# ttl_adapter.net
KiCad netlist of a schematic drawn in EAGLE
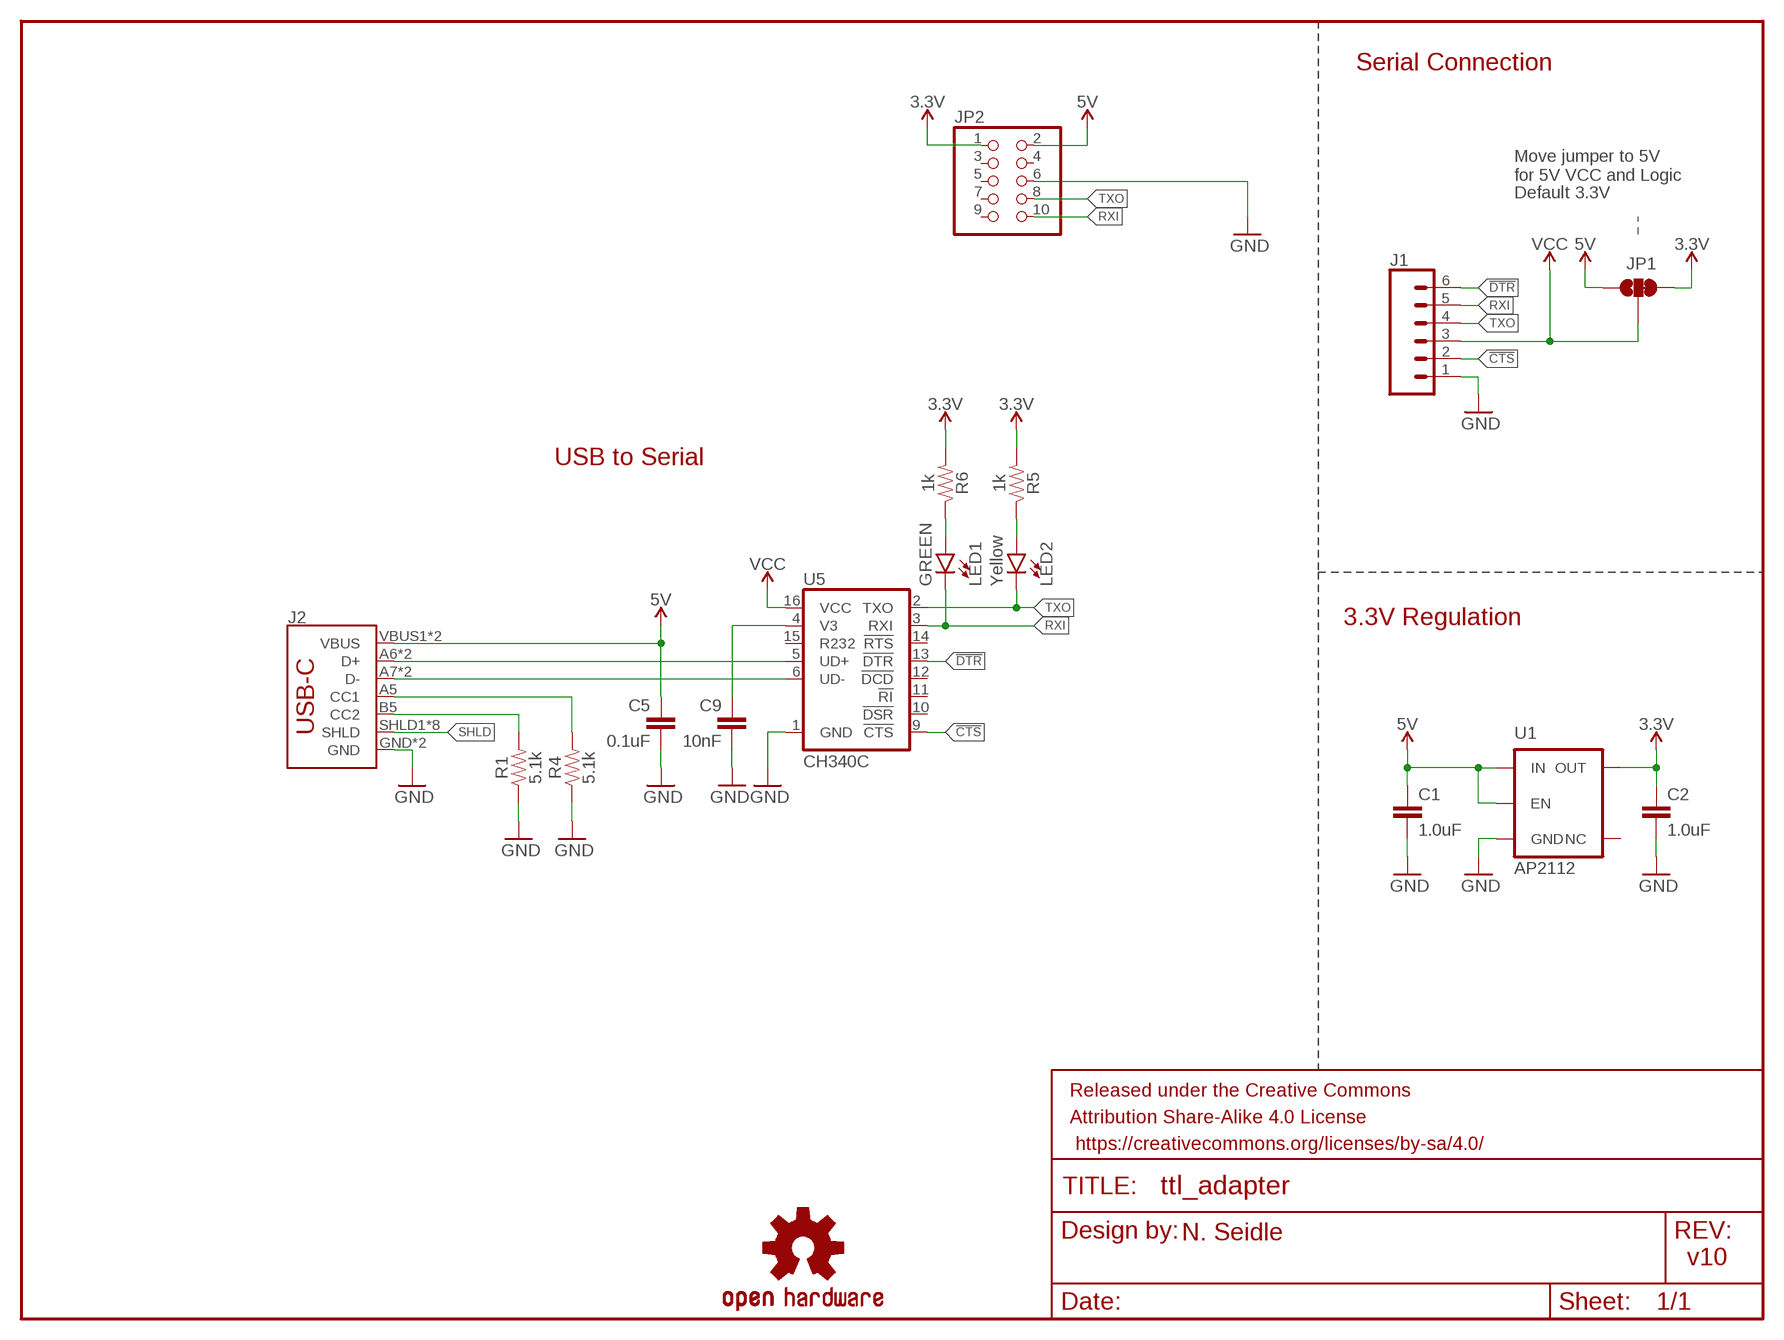
[diagram p0: schematic, sheet 1]

(export (version "E")
  (design (tool "Eeschema 10.0.6"))
  (components
    (comp (ref "C1")
      (value "1.0uF")
      (footprint "eagle-import:0603")
      (libsource (lib "eagle-import") (part "1.0UF-0603-16V-10%"))
    )
    (comp (ref "C2")
      (value "1.0uF")
      (footprint "eagle-import:0603")
      (libsource (lib "eagle-import") (part "1.0UF-0603-16V-10%"))
    )
    (comp (ref "C5")
      (value "0.1uF")
      (footprint "eagle-import:0603")
      (libsource (lib "eagle-import") (part "0.1UF-0603-25V-(+80/-20%)"))
    )
    (comp (ref "C9")
      (value "10nF")
      (footprint "eagle-import:0603")
      (libsource (lib "eagle-import") (part "10NF-0603-50V-10%"))
    )
    (comp (ref "FRAME1")
      (value "FRAME-LETTER")
      (footprint "eagle-import:CREATIVE_COMMONS")
      (libsource (lib "eagle-import") (part "FRAME-LETTER"))
    )
    (comp (ref "J1")
      (value "CONN_06SMD-FEMALE-V2")
      (footprint "eagle-import:1X06-SMD-FEMALE")
      (libsource (lib "eagle-import") (part "CONN_06SMD-FEMALE-V2"))
    )
    (comp (ref "J2")
      (value "USB_C16PIN")
      (footprint "eagle-import:USB-C-16P")
      (libsource (lib "eagle-import") (part "USB_C16PIN"))
    )
    (comp (ref "JP1")
      (value "JUMPER-SMT_3_1-NC_TRACE_SILK")
      (footprint "eagle-import:SMT-JUMPER_3_1-NC_TRACE_SILK")
      (libsource (lib "eagle-import") (part "JUMPER-SMT_3_1-NC_TRACE_SILK"))
    )
    (comp (ref "JP2")
      (value "PINHD-2X5")
      (footprint "eagle-import:2X05")
      (libsource (lib "eagle-import") (part "PINHD-2X5"))
    )
    (comp (ref "LED1")
      (value "GREEN")
      (footprint "eagle-import:LED-0603")
      (libsource (lib "eagle-import") (part "LED-GREEN0603"))
    )
    (comp (ref "LED2")
      (value "Yellow")
      (footprint "eagle-import:LED-0603")
      (libsource (lib "eagle-import") (part "LED-YELLOW0603"))
    )
    (comp (ref "LOGO1")
      (value "OSHW-LOGOS")
      (footprint "eagle-import:OSHW-LOGO-S")
      (libsource (lib "eagle-import") (part "OSHW-LOGOS"))
    )
    (comp (ref "R1")
      (value "5.1k")
      (footprint "eagle-import:0603")
      (libsource (lib "eagle-import") (part "5.1KOHM5.1KOHM-0603-1/10W-1%"))
    )
    (comp (ref "R4")
      (value "5.1k")
      (footprint "eagle-import:0603")
      (libsource (lib "eagle-import") (part "5.1KOHM5.1KOHM-0603-1/10W-1%"))
    )
    (comp (ref "R5")
      (value "1k")
      (footprint "eagle-import:0603")
      (libsource (lib "eagle-import") (part "1KOHM-0603-1/10W-1%"))
    )
    (comp (ref "R6")
      (value "1k")
      (footprint "eagle-import:0603")
      (libsource (lib "eagle-import") (part "1KOHM-0603-1/10W-1%"))
    )
    (comp (ref "U1")
      (value "3.3V")
      (footprint "eagle-import:SOT23-5")
      (libsource (lib "eagle-import") (part "V_REG_AP2112K-3.3V"))
    )
    (comp (ref "U5")
      (value "CH340C")
      (footprint "eagle-import:SO016")
      (libsource (lib "eagle-import") (part "CH340C"))
    )
  )
  (nets
    (net (code "1") (name "/~{CTS}") (class "Default")
      (node (ref "J1") (pin "2") (pinfunction "2_2") (pintype "passive"))
      (node (ref "U5") (pin "9") (pinfunction "~{CTS}_9") (pintype "bidirectional"))
    )
    (net (code "2") (name "/~{DTR}") (class "Default")
      (node (ref "J1") (pin "6") (pinfunction "6_6") (pintype "passive"))
      (node (ref "U5") (pin "13") (pinfunction "~{DTR}_13") (pintype "bidirectional"))
    )
    (net (code "3") (name "3.3V") (class "Default")
      (node (ref "C2") (pin "1") (pinfunction "1_1") (pintype "passive"))
      (node (ref "JP1") (pin "3") (pinfunction "3_3") (pintype "passive"))
      (node (ref "JP2") (pin "1") (pinfunction "1_1") (pintype "passive"))
      (node (ref "R5") (pin "2") (pinfunction "2_2") (pintype "passive"))
      (node (ref "R6") (pin "2") (pinfunction "2_2") (pintype "passive"))
      (node (ref "U1") (pin "5") (pinfunction "OUT_5") (pintype "passive"))
    )
    (net (code "4") (name "5V") (class "Default")
      (node (ref "C1") (pin "1") (pinfunction "1_1") (pintype "passive"))
      (node (ref "C5") (pin "1") (pinfunction "1_1") (pintype "passive"))
      (node (ref "J2") (pin "VBUS1") (pinfunction "VBUS_VBUS1") (pintype "bidirectional"))
      (node (ref "J2") (pin "VBUS2") (pinfunction "VBUS_VBUS2") (pintype "bidirectional"))
      (node (ref "JP1") (pin "1") (pinfunction "1_1") (pintype "passive"))
      (node (ref "JP2") (pin "2") (pinfunction "2_2") (pintype "passive"))
      (node (ref "U1") (pin "1") (pinfunction "IN_1") (pintype "input"))
      (node (ref "U1") (pin "3") (pinfunction "EN_3") (pintype "input"))
    )
    (net (code "5") (name "GND") (class "Default")
      (node (ref "C1") (pin "2") (pinfunction "2_2") (pintype "passive"))
      (node (ref "C2") (pin "2") (pinfunction "2_2") (pintype "passive"))
      (node (ref "C5") (pin "2") (pinfunction "2_2") (pintype "passive"))
      (node (ref "C9") (pin "2") (pinfunction "2_2") (pintype "passive"))
      (node (ref "J1") (pin "1") (pinfunction "1_1") (pintype "passive"))
      (node (ref "J2") (pin "GND") (pinfunction "GND_GND") (pintype "bidirectional"))
      (node (ref "J2") (pin "GND2") (pinfunction "GND_GND2") (pintype "bidirectional"))
      (node (ref "JP2") (pin "6") (pinfunction "6_6") (pintype "passive"))
      (node (ref "R1") (pin "1") (pinfunction "1_1") (pintype "passive"))
      (node (ref "R4") (pin "1") (pinfunction "1_1") (pintype "passive"))
      (node (ref "U1") (pin "2") (pinfunction "GND_2") (pintype "input"))
      (node (ref "U5") (pin "1") (pinfunction "GND_1") (pintype "bidirectional"))
    )
    (net (code "6") (name "Net-(J2-CC1)") (class "Default")
      (node (ref "J2") (pin "A5") (pinfunction "CC1_A5") (pintype "bidirectional"))
      (node (ref "R4") (pin "2") (pinfunction "2_2") (pintype "passive"))
    )
    (net (code "7") (name "Net-(J2-CC2)") (class "Default")
      (node (ref "J2") (pin "B5") (pinfunction "CC2_B5") (pintype "bidirectional"))
      (node (ref "R1") (pin "2") (pinfunction "2_2") (pintype "passive"))
    )
    (net (code "8") (name "Net-(LED1-PadA)") (class "Default")
      (node (ref "LED1") (pin "A") (pinfunction "A_A") (pintype "passive"))
      (node (ref "R6") (pin "1") (pinfunction "1_1") (pintype "passive"))
    )
    (net (code "9") (name "Net-(LED2-PadA)") (class "Default")
      (node (ref "LED2") (pin "A") (pinfunction "A_A") (pintype "passive"))
      (node (ref "R5") (pin "1") (pinfunction "1_1") (pintype "passive"))
    )
    (net (code "10") (name "Net-(U5-UD+)") (class "Default")
      (node (ref "J2") (pin "A6") (pinfunction "D+_A6") (pintype "bidirectional"))
      (node (ref "J2") (pin "B6") (pinfunction "D+_B6") (pintype "bidirectional"))
      (node (ref "U5") (pin "5") (pinfunction "UD+_5") (pintype "bidirectional"))
    )
    (net (code "11") (name "Net-(U5-UD-)") (class "Default")
      (node (ref "J2") (pin "A7") (pinfunction "D-_A7") (pintype "bidirectional"))
      (node (ref "J2") (pin "B7") (pinfunction "D-_B7") (pintype "bidirectional"))
      (node (ref "U5") (pin "6") (pinfunction "UD-_6") (pintype "bidirectional"))
    )
    (net (code "12") (name "Net-(U5-V3)") (class "Default")
      (node (ref "C9") (pin "1") (pinfunction "1_1") (pintype "passive"))
      (node (ref "U5") (pin "4") (pinfunction "V3_4") (pintype "bidirectional"))
    )
    (net (code "13") (name "RXI") (class "Default")
      (node (ref "J1") (pin "5") (pinfunction "5_5") (pintype "passive"))
      (node (ref "JP2") (pin "10") (pinfunction "10_10") (pintype "passive"))
      (node (ref "LED1") (pin "C") (pinfunction "C_C") (pintype "passive"))
      (node (ref "U5") (pin "3") (pinfunction "RXI_3") (pintype "bidirectional"))
    )
    (net (code "14") (name "SHLD") (class "Default")
      (node (ref "J2") (pin "SHLD1") (pinfunction "SHLD_SHLD1") (pintype "bidirectional"))
      (node (ref "J2") (pin "SHLD2") (pinfunction "SHLD_SHLD2") (pintype "bidirectional"))
      (node (ref "J2") (pin "SHLD3") (pinfunction "SHLD_SHLD3") (pintype "bidirectional"))
      (node (ref "J2") (pin "SHLD4") (pinfunction "SHLD_SHLD4") (pintype "bidirectional"))
      (node (ref "J2") (pin "SHLD5") (pinfunction "SHLD_SHLD5") (pintype "bidirectional"))
      (node (ref "J2") (pin "SHLD6") (pinfunction "SHLD_SHLD6") (pintype "bidirectional"))
      (node (ref "J2") (pin "SHLD7") (pinfunction "SHLD_SHLD7") (pintype "bidirectional"))
      (node (ref "J2") (pin "SHLD8") (pinfunction "SHLD_SHLD8") (pintype "bidirectional"))
    )
    (net (code "15") (name "TXO") (class "Default")
      (node (ref "J1") (pin "4") (pinfunction "4_4") (pintype "passive"))
      (node (ref "JP2") (pin "8") (pinfunction "8_8") (pintype "passive"))
      (node (ref "LED2") (pin "C") (pinfunction "C_C") (pintype "passive"))
      (node (ref "U5") (pin "2") (pinfunction "TXO_2") (pintype "bidirectional"))
    )
    (net (code "16") (name "VCC") (class "Default")
      (node (ref "J1") (pin "3") (pinfunction "3_3") (pintype "passive"))
      (node (ref "JP1") (pin "2") (pinfunction "2_2") (pintype "passive"))
      (node (ref "U5") (pin "16") (pinfunction "VCC_16") (pintype "bidirectional"))
    )
    (net (code "17") (name "unconnected-(JP2-Pad3)") (class "Default")
      (node (ref "JP2") (pin "3") (pinfunction "3_3") (pintype "passive"))
    )
    (net (code "18") (name "unconnected-(JP2-Pad4)") (class "Default")
      (node (ref "JP2") (pin "4") (pinfunction "4_4") (pintype "passive"))
    )
    (net (code "19") (name "unconnected-(JP2-Pad5)") (class "Default")
      (node (ref "JP2") (pin "5") (pinfunction "5_5") (pintype "passive"))
    )
    (net (code "20") (name "unconnected-(JP2-Pad7)") (class "Default")
      (node (ref "JP2") (pin "7") (pinfunction "7_7") (pintype "passive"))
    )
    (net (code "21") (name "unconnected-(JP2-Pad9)") (class "Default")
      (node (ref "JP2") (pin "9") (pinfunction "9_9") (pintype "passive"))
    )
    (net (code "22") (name "unconnected-(U1-NC-Pad4)") (class "Default")
      (node (ref "U1") (pin "4") (pinfunction "NC_4") (pintype "no_connect"))
    )
    (net (code "23") (name "unconnected-(U5-R232-Pad15)") (class "Default")
      (node (ref "U5") (pin "15") (pinfunction "R232_15") (pintype "bidirectional"))
    )
    (net (code "24") (name "unconnected-(U5-~{DCD}-Pad12)") (class "Default")
      (node (ref "U5") (pin "12") (pinfunction "~{DCD}_12") (pintype "bidirectional"))
    )
    (net (code "25") (name "unconnected-(U5-~{DSR}-Pad10)") (class "Default")
      (node (ref "U5") (pin "10") (pinfunction "~{DSR}_10") (pintype "bidirectional"))
    )
    (net (code "26") (name "unconnected-(U5-~{RI}-Pad11)") (class "Default")
      (node (ref "U5") (pin "11") (pinfunction "~{RI}_11") (pintype "bidirectional"))
    )
    (net (code "27") (name "unconnected-(U5-~{RTS}-Pad14)") (class "Default")
      (node (ref "U5") (pin "14") (pinfunction "~{RTS}_14") (pintype "bidirectional"))
    )
  )
)
